# LowFreqSignal.net
KiCad netlist of a schematic drawn in Altium Designer
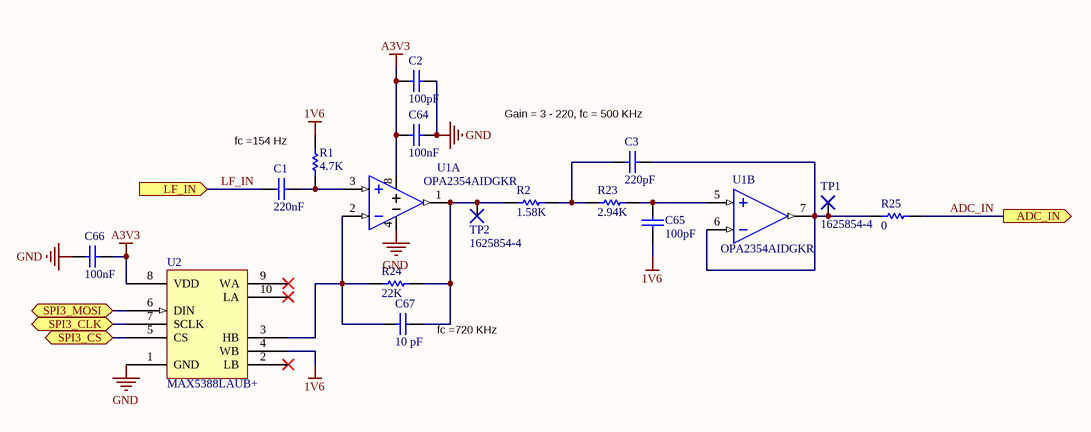
[diagram p0: LowFreqSignal.SchDoc]

(export (version "E")
  (design (tool "Eeschema 10.0.6"))
  (components
    (comp (ref "C1")
      (value "220nF")
      (footprint "0603 Cap")
      (description "CAP CER 0.22UF 16V X7R 0603")
      (fields
        (field (name "MANUFACTURER") "TDK Corporation")
        (field (name "MANUFACTURER PART NUMBER") "C1608X7R1C224K080AC")
      )
      (libsource (lib "Componentes_base") (part "C1608X7R1C224K080AC"))
    )
    (comp (ref "C2")
      (value "100pF")
      (footprint "0603 Cap")
      (description "CAP CER 100PF 50V X7R 0603")
      (fields
        (field (name "MANUFACTURER") "Samsung Electro-Mechanics America, Inc.")
        (field (name "MANUFACTURER PART NUMBER") "CL10B101KB8NNNC")
      )
      (libsource (lib "Componentes_base") (part "CL10B101KB8NNNC"))
    )
    (comp (ref "C3")
      (value "220pF")
      (footprint "0603 Cap")
      (description "CAP CER 220PF 50V X7R 0603")
      (fields
        (field (name "MANUFACTURER") "Samsung Electro-Mechanics America, Inc.")
        (field (name "MANUFACTURER PART NUMBER") "CL10B221KB8WPNC")
      )
      (libsource (lib "Componentes_base") (part "CL10B221KB8WPNC"))
    )
    (comp (ref "C64")
      (value "100nF")
      (footprint "0603 Cap")
      (description "CAP CER 0.1UF 16V X7R 0603")
      (fields
        (field (name "MANUFACTURER") "KEMET")
        (field (name "MANUFACTURER PART NUMBER") "C0603C104K4RACTU")
      )
      (libsource (lib "Componentes_base") (part "C0603C104K4RACTU"))
    )
    (comp (ref "C65")
      (value "100pF")
      (footprint "0603 Cap")
      (description "CAP CER 100PF 50V X7R 0603")
      (fields
        (field (name "MANUFACTURER") "Samsung Electro-Mechanics America, Inc.")
        (field (name "MANUFACTURER PART NUMBER") "CL10B101KB8NNNC")
      )
      (libsource (lib "Componentes_base") (part "CL10B101KB8NNNC"))
    )
    (comp (ref "C66")
      (value "100nF")
      (footprint "0603 Cap")
      (description "CAP CER 0.1UF 16V X7R 0603")
      (fields
        (field (name "MANUFACTURER") "KEMET")
        (field (name "MANUFACTURER PART NUMBER") "C0603C104K4RACTU")
      )
      (libsource (lib "Componentes_base") (part "C0603C104K4RACTU"))
    )
    (comp (ref "C67")
      (value "10 pF")
      (footprint "CAPC1005X05L")
      (description "CAP CER 10PF 50V 5% NP0 0402")
      (fields
        (field (name "MANUFACTURER") "Samsung Electro-Mechanics America, Inc")
        (field (name "MANUFACTURER PART NUMBER") "CL05C100JB5NNNC")
      )
      (libsource (lib "Componentes_base") (part "CL05C100JB5NNNC"))
    )
    (comp (ref "R1")
      (value "4.7K")
      (footprint "0603 Res")
      (description "RES SMD 4.7K OHM 1% 1/10W 0603")
      (fields
        (field (name "MANUFACTURER") "Yageo")
        (field (name "MANUFACTURER PART NUMBER") "RC0603FR-074K7L")
      )
      (libsource (lib "Componentes_base") (part "RC0603FR-074K7L"))
    )
    (comp (ref "R2")
      (value "1.58K")
      (footprint "0603 Res")
      (description "RES SMD 1.58K OHM 1% 1/10W 0603")
      (fields
        (field (name "MANUFACTURER") "Yageo")
        (field (name "MANUFACTURER PART NUMBER") "RC0603FR-071K58L")
      )
      (libsource (lib "Componentes_base") (part "RC0603FR-071K58L"))
    )
    (comp (ref "R23")
      (value "2.94K")
      (footprint "0603 Res")
      (description "RES SMD 2.94K OHM 1% 1/10W 0603")
      (fields
        (field (name "MANUFACTURER") "Yageo")
        (field (name "MANUFACTURER PART NUMBER") "RC0603FR-072K94L")
      )
      (libsource (lib "Componentes_base") (part "RC0603FR-072K94L"))
    )
    (comp (ref "R24")
      (value "22K")
      (footprint "0603 Res")
      (description "RES SMD 22K OHM 1% 1/10W 0603")
      (fields
        (field (name "MANUFACTURER") "Yageo")
        (field (name "MANUFACTURER PART NUMBER") "RC0603FR-0722KL")
      )
      (libsource (lib "Componentes_base") (part "RC0603FR-0722KL"))
    )
    (comp (ref "R25")
      (value "0")
      (footprint "RESC1005X04L")
      (description "RES 0.0 OHM 1/16W JUMP 0402")
      (fields
        (field (name "MANUFACTURER") "Samsung Electro-Mechanics America, Inc")
        (field (name "MANUFACTURER PART NUMBER") "RC1005J000CS")
      )
      (libsource (lib "Componentes_base") (part "RC1005J000CS"))
    )
    (comp (ref "TP1")
      (value "1625854-4")
      (footprint "TESTPOINT 1206")
      (description "1206 PROBE PAD")
      (fields (field (name "MANUFACTURER") "TE Connectivity AMP Connectors"))
      (libsource (lib "Componentes_base") (part "1625854-4"))
    )
    (comp (ref "TP2")
      (value "1625854-4")
      (footprint "TESTPOINT 1206")
      (description "1206 PROBE PAD")
      (fields (field (name "MANUFACTURER") "TE Connectivity AMP Connectors"))
      (libsource (lib "Componentes_base") (part "1625854-4"))
    )
    (comp (ref "U1")
      (value "OPA2354AIDGKR")
      (footprint "MSOP-8")
      (description "IC OPAMP VFB 100MHZ RRO 8VSSOP")
      (fields (field (name "MANUFACTURER") "Texas Instruments"))
      (libsource (lib "Componentes_base") (part "OPA2354AIDGKR"))
    )
    (comp (ref "U2")
      (value "MAX5388LAUB+")
      (footprint "uSOP-10 uMAX")
      (description "IC DGTL POT 256POS 10K 10UMAX")
      (fields (field (name "MANUFACTURER") "Maxim Integrated") (field (name "TOLERANCE") "±25%"))
      (libsource (lib "Componentes_base") (part "MAX5388LAUB+"))
    )
  )
  (nets
    (net (code "1") (name "/ADC_IN") (class "Default")
      (node (ref "R25") (pin "2") (pinfunction "2_2") (pintype "passive"))
    )
    (net (code "2") (name "/LF_IN") (class "Default")
      (node (ref "C1") (pin "1") (pinfunction "1_1") (pintype "passive"))
    )
    (net (code "3") (name "/SPI3_CLK") (class "Default")
      (node (ref "U2") (pin "7") (pinfunction "SCLK_7") (pintype "passive"))
    )
    (net (code "4") (name "/SPI3_CS") (class "Default")
      (node (ref "U2") (pin "5") (pinfunction "CS_5") (pintype "passive"))
    )
    (net (code "5") (name "/SPI3_MOSI") (class "Default")
      (node (ref "U2") (pin "6") (pinfunction "DIN_6") (pintype "input"))
    )
    (net (code "6") (name "1V6") (class "Default")
      (node (ref "C65") (pin "1") (pinfunction "1_1") (pintype "passive"))
      (node (ref "R1") (pin "2") (pinfunction "2_2") (pintype "passive"))
      (node (ref "U2") (pin "4") (pinfunction "WB_4") (pintype "passive"))
    )
    (net (code "7") (name "A3V3") (class "Default")
      (node (ref "C2") (pin "1") (pinfunction "1_1") (pintype "passive"))
      (node (ref "C64") (pin "1") (pinfunction "1_1") (pintype "passive"))
      (node (ref "C66") (pin "2") (pinfunction "2_2") (pintype "passive"))
      (node (ref "U1") (pin "8") (pinfunction "V+_8") (pintype "power_in"))
      (node (ref "U2") (pin "8") (pinfunction "VDD_8") (pintype "power_in"))
    )
    (net (code "8") (name "GND") (class "Default")
      (node (ref "C2") (pin "2") (pinfunction "2_2") (pintype "passive"))
      (node (ref "C64") (pin "2") (pinfunction "2_2") (pintype "passive"))
      (node (ref "C66") (pin "1") (pinfunction "1_1") (pintype "passive"))
      (node (ref "U1") (pin "4") (pinfunction "V-_4") (pintype "power_in"))
      (node (ref "U2") (pin "1") (pinfunction "GND_1") (pintype "power_in"))
    )
    (net (code "9") (name "Net-(C3-Pad2)") (class "Default")
      (node (ref "C3") (pin "2") (pinfunction "2_2") (pintype "passive"))
      (node (ref "R2") (pin "2") (pinfunction "2_2") (pintype "passive"))
      (node (ref "R23") (pin "1") (pinfunction "1_1") (pintype "passive"))
    )
    (net (code "10") (name "Net-(U1A-IN+A)") (class "Default")
      (node (ref "C1") (pin "2") (pinfunction "2_2") (pintype "passive"))
      (node (ref "R1") (pin "1") (pinfunction "1_1") (pintype "passive"))
      (node (ref "U1") (pin "3") (pinfunction "IN+A_3") (pintype "input"))
    )
    (net (code "11") (name "Net-(U1A-IN-A)") (class "Default")
      (node (ref "C67") (pin "1") (pinfunction "1_1") (pintype "passive"))
      (node (ref "R24") (pin "1") (pinfunction "1_1") (pintype "passive"))
      (node (ref "U1") (pin "2") (pinfunction "IN-A_2") (pintype "input"))
      (node (ref "U2") (pin "3") (pinfunction "HB_3") (pintype "passive"))
    )
    (net (code "12") (name "Net-(U1A-OUTA)") (class "Default")
      (node (ref "C67") (pin "2") (pinfunction "2_2") (pintype "passive"))
      (node (ref "R2") (pin "1") (pinfunction "1_1") (pintype "passive"))
      (node (ref "R24") (pin "2") (pinfunction "2_2") (pintype "passive"))
      (node (ref "TP2") (pin "1") (pinfunction "1_1") (pintype "passive"))
      (node (ref "U1") (pin "1") (pinfunction "OUTA_1") (pintype "output"))
    )
    (net (code "13") (name "Net-(U1B-IN+B)") (class "Default")
      (node (ref "C65") (pin "2") (pinfunction "2_2") (pintype "passive"))
      (node (ref "R23") (pin "2") (pinfunction "2_2") (pintype "passive"))
      (node (ref "U1") (pin "5") (pinfunction "IN+B_5") (pintype "input"))
    )
    (net (code "14") (name "Net-(U1B-IN-B)") (class "Default")
      (node (ref "C3") (pin "1") (pinfunction "1_1") (pintype "passive"))
      (node (ref "R25") (pin "1") (pinfunction "1_1") (pintype "passive"))
      (node (ref "TP1") (pin "1") (pinfunction "1_1") (pintype "passive"))
      (node (ref "U1") (pin "6") (pinfunction "IN-B_6") (pintype "input"))
      (node (ref "U1") (pin "7") (pinfunction "OUTB_7") (pintype "output"))
    )
    (net (code "15") (name "unconnected-(U2-LA-Pad10)") (class "Default")
      (node (ref "U2") (pin "10") (pinfunction "LA_10") (pintype "passive+no_connect"))
    )
    (net (code "16") (name "unconnected-(U2-LB-Pad2)") (class "Default")
      (node (ref "U2") (pin "2") (pinfunction "LB_2") (pintype "passive+no_connect"))
    )
    (net (code "17") (name "unconnected-(U2-WA-Pad9)") (class "Default")
      (node (ref "U2") (pin "9") (pinfunction "WA_9") (pintype "passive+no_connect"))
    )
  )
)
